# kalypso-usb-v1.net
KiCad netlist of a schematic drawn in EAGLE
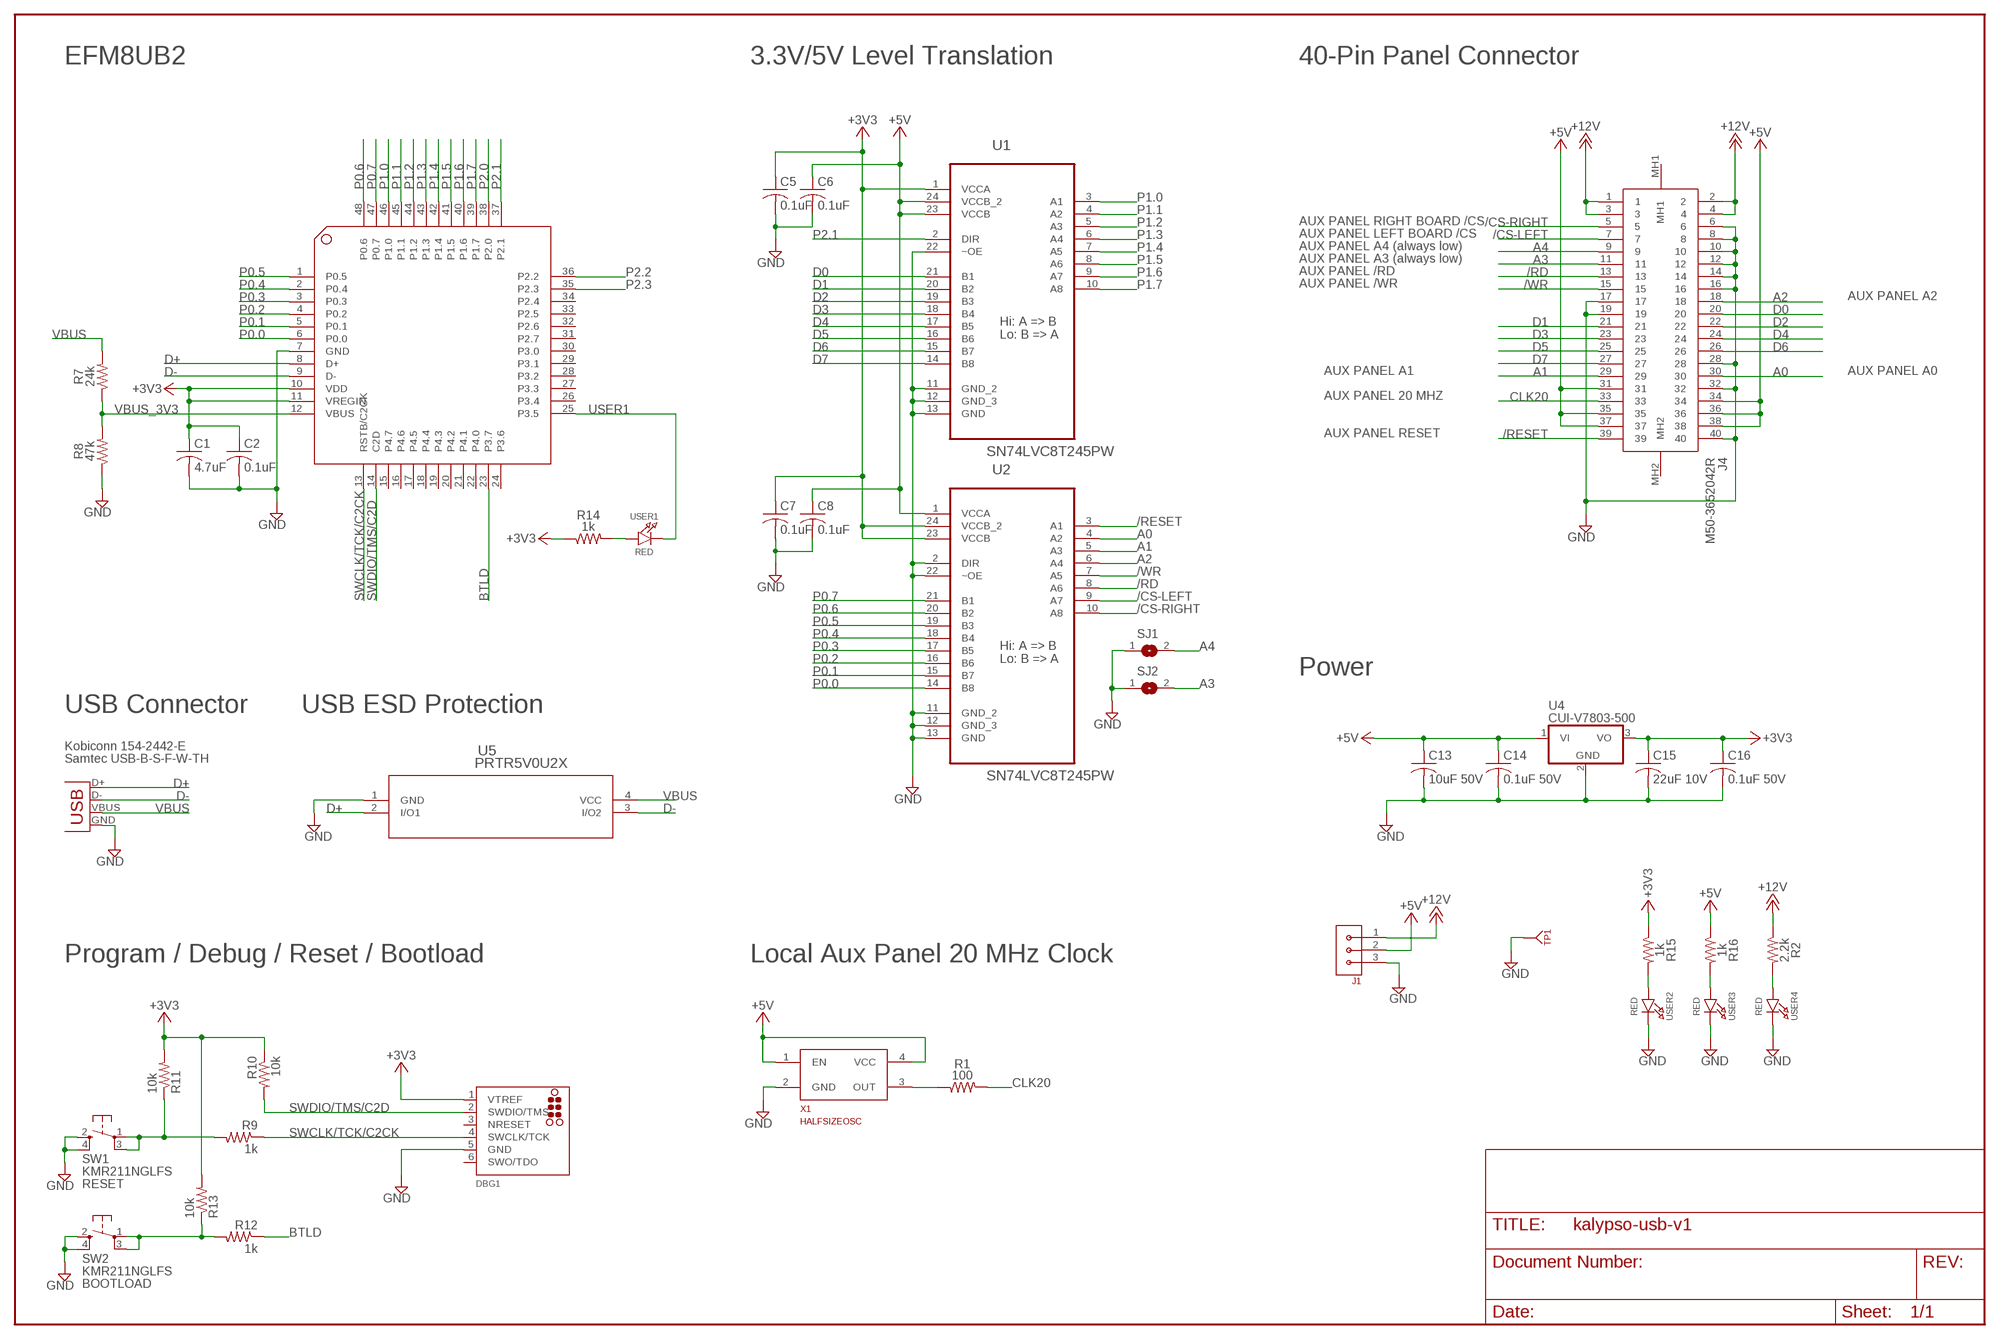
[diagram p0: schematic, sheet 1]

(export (version "E")
  (design (tool "Eeschema 10.0.6"))
  (components
    (comp (ref "C1")
      (value "4.7uF")
      (footprint "eagle-import:C0805K")
      (libsource (lib "eagle-import") (part "C-USC0805K"))
    )
    (comp (ref "C2")
      (value "0.1uF")
      (footprint "eagle-import:C0603K")
      (libsource (lib "eagle-import") (part "C-USC0603K"))
    )
    (comp (ref "C5")
      (value "0.1uF")
      (footprint "eagle-import:C0603K")
      (libsource (lib "eagle-import") (part "C-USC0603K"))
    )
    (comp (ref "C6")
      (value "0.1uF")
      (footprint "eagle-import:C0603K")
      (libsource (lib "eagle-import") (part "C-USC0603K"))
    )
    (comp (ref "C7")
      (value "0.1uF")
      (footprint "eagle-import:C0603K")
      (libsource (lib "eagle-import") (part "C-USC0603K"))
    )
    (comp (ref "C8")
      (value "0.1uF")
      (footprint "eagle-import:C0603K")
      (libsource (lib "eagle-import") (part "C-USC0603K"))
    )
    (comp (ref "C13")
      (value "10uF 50V")
      (footprint "eagle-import:C1210K")
      (fields (field (name "MFR") "KEMET") (field (name "MFR_PART_NO") "C1210C106K5RACTU"))
      (libsource (lib "eagle-import") (part "C-USC1210K"))
    )
    (comp (ref "C14")
      (value "0.1uF 50V")
      (footprint "eagle-import:C1206K")
      (fields (field (name "MFR") "KEMET") (field (name "MFR_PART_NO") "C1206S104M5RACTU"))
      (libsource (lib "eagle-import") (part "C-USC1206K"))
    )
    (comp (ref "C15")
      (value "22uF 10V")
      (footprint "eagle-import:C1206K")
      (fields (field (name "MFR") "KEMET") (field (name "MFR_PART_NO") "C1206C226K8RAC7800"))
      (libsource (lib "eagle-import") (part "C-USC1206K"))
    )
    (comp (ref "C16")
      (value "0.1uF 50V")
      (footprint "eagle-import:C1206K")
      (fields (field (name "MFR") "KEMET") (field (name "MFR_PART_NO") "C1206S104M5RACTU"))
      (libsource (lib "eagle-import") (part "C-USC1206K"))
    )
    (comp (ref "DBG1")
      (value "TC2030-CTX-SWD")
      (footprint "eagle-import:TC2030-MCP-NL")
      (libsource (lib "eagle-import") (part "TC2030-CTX-SWD"))
    )
    (comp (ref "J1")
      (value "CON-3.81MM-1X3-PHOENIX-RA")
      (footprint "eagle-import:CON-PHOENIX-3.81-1X3-RA")
      (libsource (lib "eagle-import") (part "CON-3.81MM-1X3-PHOENIX-RA"))
    )
    (comp (ref "J2")
      (value "USB-B")
      (footprint "eagle-import:USB-B-PTH")
      (fields (field (name "MFR") "KOBICONN") (field (name "MFR_PART_NO") "154-2442-E"))
      (libsource (lib "eagle-import") (part "USBPTH"))
    )
    (comp (ref "J4")
      (value "M50-3652042R")
      (footprint "eagle-import:M503652042R")
      (fields (field (name "MOUSER_PART_NUMBER") "855-M50-3652042R"))
      (libsource (lib "eagle-import") (part "M50-3652042R"))
    )
    (comp (ref "R1")
      (value "100")
      (footprint "eagle-import:R0603")
      (libsource (lib "eagle-import") (part "R-US_R0603"))
    )
    (comp (ref "R2")
      (value "2.2k")
      (footprint "eagle-import:R0603")
      (libsource (lib "eagle-import") (part "R-US_R0603"))
    )
    (comp (ref "R7")
      (value "24k")
      (footprint "eagle-import:R0603")
      (libsource (lib "eagle-import") (part "R-US_R0603"))
    )
    (comp (ref "R8")
      (value "47k")
      (footprint "eagle-import:R0603")
      (libsource (lib "eagle-import") (part "R-US_R0603"))
    )
    (comp (ref "R9")
      (value "1k")
      (footprint "eagle-import:R0603")
      (libsource (lib "eagle-import") (part "R-US_R0603"))
    )
    (comp (ref "R10")
      (value "10k")
      (footprint "eagle-import:R0603")
      (libsource (lib "eagle-import") (part "R-US_R0603"))
    )
    (comp (ref "R11")
      (value "10k")
      (footprint "eagle-import:R0603")
      (libsource (lib "eagle-import") (part "R-US_R0603"))
    )
    (comp (ref "R12")
      (value "1k")
      (footprint "eagle-import:R0603")
      (libsource (lib "eagle-import") (part "R-US_R0603"))
    )
    (comp (ref "R13")
      (value "10k")
      (footprint "eagle-import:R0603")
      (libsource (lib "eagle-import") (part "R-US_R0603"))
    )
    (comp (ref "R14")
      (value "1k")
      (footprint "eagle-import:R0603")
      (libsource (lib "eagle-import") (part "R-US_R0603"))
    )
    (comp (ref "R15")
      (value "1k")
      (footprint "eagle-import:R0603")
      (libsource (lib "eagle-import") (part "R-US_R0603"))
    )
    (comp (ref "R16")
      (value "1k")
      (footprint "eagle-import:R0603")
      (libsource (lib "eagle-import") (part "R-US_R0603"))
    )
    (comp (ref "SJ1") (value "SJ") (footprint "eagle-import:SJ") (libsource (lib "eagle-import") (part "SJ")))
    (comp (ref "SJ2") (value "SJ") (footprint "eagle-import:SJ") (libsource (lib "eagle-import") (part "SJ")))
    (comp (ref "SW1")
      (value "KMR211NGLFS")
      (footprint "eagle-import:KMR2")
      (libsource (lib "eagle-import") (part "SPST_TACT-KMR2"))
    )
    (comp (ref "SW2")
      (value "KMR211NGLFS")
      (footprint "eagle-import:KMR2")
      (libsource (lib "eagle-import") (part "SPST_TACT-KMR2"))
    )
    (comp (ref "TP1")
      (value "KEYSTONE_500X")
      (footprint "eagle-import:KEYSTONE_TP500X")
      (libsource (lib "eagle-import") (part "KEYSTONE_500X"))
    )
    (comp (ref "U1")
      (value "SN74LVC8T245PW")
      (footprint "eagle-import:SOP65P640X120-24N")
      (fields (field (name "MPN") "SN74AVC8T245PW"))
      (libsource (lib "eagle-import") (part "SN74AVC8T245PW"))
    )
    (comp (ref "U2")
      (value "SN74LVC8T245PW")
      (footprint "eagle-import:SOP65P640X120-24N")
      (fields (field (name "MPN") "SN74AVC8T245PW"))
      (libsource (lib "eagle-import") (part "SN74AVC8T245PW"))
    )
    (comp (ref "U4")
      (value "CUI-V7803-500")
      (footprint "eagle-import:CUI-78XX-500")
      (libsource (lib "eagle-import") (part "CUI-V7803-500"))
    )
    (comp (ref "U5")
      (value "PRTR5V0U2X")
      (footprint "eagle-import:SOT143B")
      (libsource (lib "eagle-import") (part "PRTR5V0U2X"))
    )
    (comp (ref "U6")
      (value "EFM8UB20F64G-B-QFP48")
      (footprint "eagle-import:EFM8UB2-QFP48")
      (libsource (lib "eagle-import") (part "EFM8UB20F64G-B-QFP48"))
    )
    (comp (ref "USER1")
      (value "RED")
      (footprint "eagle-import:CHIPLED_0805_NOOUTLINE")
      (libsource (lib "eagle-import") (part "LED0805_NOOUTLINE"))
    )
    (comp (ref "USER2")
      (value "RED")
      (footprint "eagle-import:CHIPLED_0805_NOOUTLINE")
      (libsource (lib "eagle-import") (part "LED0805_NOOUTLINE"))
    )
    (comp (ref "USER3")
      (value "RED")
      (footprint "eagle-import:CHIPLED_0805_NOOUTLINE")
      (libsource (lib "eagle-import") (part "LED0805_NOOUTLINE"))
    )
    (comp (ref "USER4")
      (value "RED")
      (footprint "eagle-import:CHIPLED_0805_NOOUTLINE")
      (libsource (lib "eagle-import") (part "LED0805_NOOUTLINE"))
    )
    (comp (ref "X1")
      (value "HALFSIZEOSC")
      (footprint "eagle-import:HALFSIZEOSC")
      (libsource (lib "eagle-import") (part "HALFSIZEOSC"))
    )
  )
  (nets
    (net (code "1") (name "+3V3") (class "Default")
      (node (ref "C1") (pin "1") (pinfunction "1_1") (pintype "passive"))
      (node (ref "C15") (pin "1") (pinfunction "1_1") (pintype "passive"))
      (node (ref "C16") (pin "1") (pinfunction "1_1") (pintype "passive"))
      (node (ref "C2") (pin "1") (pinfunction "1_1") (pintype "passive"))
      (node (ref "C5") (pin "1") (pinfunction "1_1") (pintype "passive"))
      (node (ref "C7") (pin "1") (pinfunction "1_1") (pintype "passive"))
      (node (ref "DBG1") (pin "1") (pinfunction "VTREF_1") (pintype "passive"))
      (node (ref "R10") (pin "1") (pinfunction "1_1") (pintype "passive"))
      (node (ref "R11") (pin "2") (pinfunction "2_2") (pintype "passive"))
      (node (ref "R13") (pin "2") (pinfunction "2_2") (pintype "passive"))
      (node (ref "R14") (pin "1") (pinfunction "1_1") (pintype "passive"))
      (node (ref "R15") (pin "1") (pinfunction "1_1") (pintype "passive"))
      (node (ref "U1") (pin "1") (pinfunction "VCCA_1") (pintype "power_in"))
      (node (ref "U2") (pin "23") (pinfunction "VCCB_23") (pintype "power_in"))
      (node (ref "U2") (pin "24") (pinfunction "VCCB_2_24") (pintype "power_in"))
      (node (ref "U4") (pin "3") (pinfunction "VO_3") (pintype "passive"))
      (node (ref "U6") (pin "10") (pinfunction "VDD_10") (pintype "bidirectional"))
      (node (ref "U6") (pin "11") (pinfunction "VREGIN_11") (pintype "bidirectional"))
    )
    (net (code "2") (name "+5V") (class "Default")
      (node (ref "C13") (pin "1") (pinfunction "1_1") (pintype "passive"))
      (node (ref "C14") (pin "1") (pinfunction "1_1") (pintype "passive"))
      (node (ref "C6") (pin "1") (pinfunction "1_1") (pintype "passive"))
      (node (ref "C8") (pin "1") (pinfunction "1_1") (pintype "passive"))
      (node (ref "J1") (pin "2") (pinfunction "2_2") (pintype "bidirectional"))
      (node (ref "J4") (pin "31") (pinfunction "31_31") (pintype "bidirectional"))
      (node (ref "J4") (pin "34") (pinfunction "34_34") (pintype "bidirectional"))
      (node (ref "J4") (pin "35") (pinfunction "35_35") (pintype "bidirectional"))
      (node (ref "J4") (pin "36") (pinfunction "36_36") (pintype "bidirectional"))
      (node (ref "J4") (pin "37") (pinfunction "37_37") (pintype "bidirectional"))
      (node (ref "J4") (pin "38") (pinfunction "38_38") (pintype "bidirectional"))
      (node (ref "R16") (pin "1") (pinfunction "1_1") (pintype "passive"))
      (node (ref "U1") (pin "23") (pinfunction "VCCB_23") (pintype "power_in"))
      (node (ref "U1") (pin "24") (pinfunction "VCCB_2_24") (pintype "power_in"))
      (node (ref "U2") (pin "1") (pinfunction "VCCA_1") (pintype "power_in"))
      (node (ref "U4") (pin "1") (pinfunction "VI_1") (pintype "input"))
      (node (ref "X1") (pin "1") (pinfunction "EN_1") (pintype "bidirectional"))
      (node (ref "X1") (pin "4") (pinfunction "VCC_4") (pintype "bidirectional"))
    )
    (net (code "3") (name "+12V") (class "Default")
      (node (ref "J1") (pin "1") (pinfunction "1_1") (pintype "bidirectional"))
      (node (ref "J4") (pin "1") (pinfunction "1_1") (pintype "bidirectional"))
      (node (ref "J4") (pin "2") (pinfunction "2_2") (pintype "bidirectional"))
      (node (ref "J4") (pin "3") (pinfunction "3_3") (pintype "bidirectional"))
      (node (ref "J4") (pin "4") (pinfunction "4_4") (pintype "bidirectional"))
      (node (ref "R2") (pin "1") (pinfunction "1_1") (pintype "passive"))
    )
    (net (code "4") (name "/A0") (class "Default")
      (node (ref "J4") (pin "30") (pinfunction "30_30") (pintype "bidirectional"))
      (node (ref "U2") (pin "4") (pinfunction "A2_4") (pintype "bidirectional"))
    )
    (net (code "5") (name "/A1") (class "Default")
      (node (ref "J4") (pin "29") (pinfunction "29_29") (pintype "bidirectional"))
      (node (ref "U2") (pin "5") (pinfunction "A3_5") (pintype "bidirectional"))
    )
    (net (code "6") (name "/A2") (class "Default")
      (node (ref "J4") (pin "18") (pinfunction "18_18") (pintype "bidirectional"))
      (node (ref "U2") (pin "6") (pinfunction "A4_6") (pintype "bidirectional"))
    )
    (net (code "7") (name "/A3") (class "Default")
      (node (ref "J4") (pin "11") (pinfunction "11_11") (pintype "bidirectional"))
      (node (ref "SJ2") (pin "2") (pinfunction "2_2") (pintype "passive"))
    )
    (net (code "8") (name "/A4") (class "Default")
      (node (ref "J4") (pin "9") (pinfunction "9_9") (pintype "bidirectional"))
      (node (ref "SJ1") (pin "2") (pinfunction "2_2") (pintype "passive"))
    )
    (net (code "9") (name "/BTLD") (class "Default")
      (node (ref "R12") (pin "1") (pinfunction "1_1") (pintype "passive"))
      (node (ref "U6") (pin "23") (pinfunction "P3.7_23") (pintype "bidirectional"))
    )
    (net (code "10") (name "/CLK20") (class "Default")
      (node (ref "J4") (pin "33") (pinfunction "33_33") (pintype "bidirectional"))
      (node (ref "R1") (pin "2") (pinfunction "2_2") (pintype "passive"))
    )
    (net (code "11") (name "/D+") (class "Default")
      (node (ref "J2") (pin "D+") (pinfunction "D+_D+") (pintype "bidirectional"))
      (node (ref "U5") (pin "2") (pinfunction "I/O1_2") (pintype "passive"))
      (node (ref "U6") (pin "8") (pinfunction "D+_8") (pintype "bidirectional"))
    )
    (net (code "12") (name "/D-") (class "Default")
      (node (ref "J2") (pin "D-") (pinfunction "D-_D-") (pintype "bidirectional"))
      (node (ref "U5") (pin "3") (pinfunction "I/O2_3") (pintype "passive"))
      (node (ref "U6") (pin "9") (pinfunction "D-_9") (pintype "bidirectional"))
    )
    (net (code "13") (name "/D0") (class "Default")
      (node (ref "J4") (pin "20") (pinfunction "20_20") (pintype "bidirectional"))
      (node (ref "U1") (pin "21") (pinfunction "B1_21") (pintype "bidirectional"))
    )
    (net (code "14") (name "/D1") (class "Default")
      (node (ref "J4") (pin "21") (pinfunction "21_21") (pintype "bidirectional"))
      (node (ref "U1") (pin "20") (pinfunction "B2_20") (pintype "bidirectional"))
    )
    (net (code "15") (name "/D2") (class "Default")
      (node (ref "J4") (pin "22") (pinfunction "22_22") (pintype "bidirectional"))
      (node (ref "U1") (pin "19") (pinfunction "B3_19") (pintype "bidirectional"))
    )
    (net (code "16") (name "/D3") (class "Default")
      (node (ref "J4") (pin "23") (pinfunction "23_23") (pintype "bidirectional"))
      (node (ref "U1") (pin "18") (pinfunction "B4_18") (pintype "bidirectional"))
    )
    (net (code "17") (name "/D4") (class "Default")
      (node (ref "J4") (pin "24") (pinfunction "24_24") (pintype "bidirectional"))
      (node (ref "U1") (pin "17") (pinfunction "B5_17") (pintype "bidirectional"))
    )
    (net (code "18") (name "/D5") (class "Default")
      (node (ref "J4") (pin "25") (pinfunction "25_25") (pintype "bidirectional"))
      (node (ref "U1") (pin "16") (pinfunction "B6_16") (pintype "bidirectional"))
    )
    (net (code "19") (name "/D6") (class "Default")
      (node (ref "J4") (pin "26") (pinfunction "26_26") (pintype "bidirectional"))
      (node (ref "U1") (pin "15") (pinfunction "B7_15") (pintype "bidirectional"))
    )
    (net (code "20") (name "/D7") (class "Default")
      (node (ref "J4") (pin "27") (pinfunction "27_27") (pintype "bidirectional"))
      (node (ref "U1") (pin "14") (pinfunction "B8_14") (pintype "bidirectional"))
    )
    (net (code "21") (name "/NRESET") (class "Default")
      (node (ref "DBG1") (pin "3") (pinfunction "NRESET_3") (pintype "power_in"))
    )
    (net (code "22") (name "/P0.0") (class "Default")
      (node (ref "U2") (pin "14") (pinfunction "B8_14") (pintype "bidirectional"))
      (node (ref "U6") (pin "6") (pinfunction "P0.0_6") (pintype "bidirectional"))
    )
    (net (code "23") (name "/P0.1") (class "Default")
      (node (ref "U2") (pin "15") (pinfunction "B7_15") (pintype "bidirectional"))
      (node (ref "U6") (pin "5") (pinfunction "P0.1_5") (pintype "bidirectional"))
    )
    (net (code "24") (name "/P0.2") (class "Default")
      (node (ref "U2") (pin "16") (pinfunction "B6_16") (pintype "bidirectional"))
      (node (ref "U6") (pin "4") (pinfunction "P0.2_4") (pintype "bidirectional"))
    )
    (net (code "25") (name "/P0.3") (class "Default")
      (node (ref "U2") (pin "17") (pinfunction "B5_17") (pintype "bidirectional"))
      (node (ref "U6") (pin "3") (pinfunction "P0.3_3") (pintype "bidirectional"))
    )
    (net (code "26") (name "/P0.4") (class "Default")
      (node (ref "U2") (pin "18") (pinfunction "B4_18") (pintype "bidirectional"))
      (node (ref "U6") (pin "2") (pinfunction "P0.4_2") (pintype "bidirectional"))
    )
    (net (code "27") (name "/P0.5") (class "Default")
      (node (ref "U2") (pin "19") (pinfunction "B3_19") (pintype "bidirectional"))
      (node (ref "U6") (pin "1") (pinfunction "P0.5_1") (pintype "bidirectional"))
    )
    (net (code "28") (name "/P0.6") (class "Default")
      (node (ref "U2") (pin "20") (pinfunction "B2_20") (pintype "bidirectional"))
      (node (ref "U6") (pin "48") (pinfunction "P0.6_48") (pintype "bidirectional"))
    )
    (net (code "29") (name "/P0.7") (class "Default")
      (node (ref "U2") (pin "21") (pinfunction "B1_21") (pintype "bidirectional"))
      (node (ref "U6") (pin "47") (pinfunction "P0.7_47") (pintype "bidirectional"))
    )
    (net (code "30") (name "/P1.0") (class "Default")
      (node (ref "U1") (pin "3") (pinfunction "A1_3") (pintype "bidirectional"))
      (node (ref "U6") (pin "46") (pinfunction "P1.0_46") (pintype "bidirectional"))
    )
    (net (code "31") (name "/P1.1") (class "Default")
      (node (ref "U1") (pin "4") (pinfunction "A2_4") (pintype "bidirectional"))
      (node (ref "U6") (pin "45") (pinfunction "P1.1_45") (pintype "bidirectional"))
    )
    (net (code "32") (name "/P1.2") (class "Default")
      (node (ref "U1") (pin "5") (pinfunction "A3_5") (pintype "bidirectional"))
      (node (ref "U6") (pin "44") (pinfunction "P1.2_44") (pintype "bidirectional"))
    )
    (net (code "33") (name "/P1.3") (class "Default")
      (node (ref "U1") (pin "6") (pinfunction "A4_6") (pintype "bidirectional"))
      (node (ref "U6") (pin "43") (pinfunction "P1.3_43") (pintype "bidirectional"))
    )
    (net (code "34") (name "/P1.4") (class "Default")
      (node (ref "U1") (pin "7") (pinfunction "A5_7") (pintype "bidirectional"))
      (node (ref "U6") (pin "42") (pinfunction "P1.4_42") (pintype "bidirectional"))
    )
    (net (code "35") (name "/P1.5") (class "Default")
      (node (ref "U1") (pin "8") (pinfunction "A6_8") (pintype "bidirectional"))
      (node (ref "U6") (pin "41") (pinfunction "P1.5_41") (pintype "bidirectional"))
    )
    (net (code "36") (name "/P1.6") (class "Default")
      (node (ref "U1") (pin "9") (pinfunction "A7_9") (pintype "bidirectional"))
      (node (ref "U6") (pin "40") (pinfunction "P1.6_40") (pintype "bidirectional"))
    )
    (net (code "37") (name "/P1.7") (class "Default")
      (node (ref "U1") (pin "10") (pinfunction "A8_10") (pintype "bidirectional"))
      (node (ref "U6") (pin "39") (pinfunction "P1.7_39") (pintype "bidirectional"))
    )
    (net (code "38") (name "/P2.0") (class "Default")
      (node (ref "U6") (pin "38") (pinfunction "P2.0_38") (pintype "bidirectional"))
    )
    (net (code "39") (name "/P2.1") (class "Default")
      (node (ref "U1") (pin "2") (pinfunction "DIR_2") (pintype "input"))
      (node (ref "U6") (pin "37") (pinfunction "P2.1_37") (pintype "bidirectional"))
    )
    (net (code "40") (name "/P2.2") (class "Default")
      (node (ref "U6") (pin "36") (pinfunction "P2.2_36") (pintype "bidirectional"))
    )
    (net (code "41") (name "/P2.3") (class "Default")
      (node (ref "U6") (pin "35") (pinfunction "P2.3_35") (pintype "bidirectional"))
    )
    (net (code "42") (name "/SWCLK{slash}TCK{slash}C2CK") (class "Default")
      (node (ref "DBG1") (pin "4") (pinfunction "SWCLK/TCK_4") (pintype "bidirectional"))
      (node (ref "R9") (pin "1") (pinfunction "1_1") (pintype "passive"))
      (node (ref "U6") (pin "13") (pinfunction "RSTB/C2CK_13") (pintype "bidirectional"))
    )
    (net (code "43") (name "/SWDIO{slash}TMS{slash}C2D") (class "Default")
      (node (ref "DBG1") (pin "2") (pinfunction "SWDIO/TMS_2") (pintype "power_in"))
      (node (ref "R10") (pin "2") (pinfunction "2_2") (pintype "passive"))
      (node (ref "U6") (pin "14") (pinfunction "C2D_14") (pintype "bidirectional"))
    )
    (net (code "44") (name "/USER1") (class "Default")
      (node (ref "U6") (pin "25") (pinfunction "P3.5_25") (pintype "bidirectional"))
      (node (ref "USER1") (pin "C") (pinfunction "C_C") (pintype "passive"))
    )
    (net (code "45") (name "/VBUS") (class "Default")
      (node (ref "J2") (pin "VBUS") (pinfunction "VBUS_VBUS") (pintype "bidirectional"))
      (node (ref "R7") (pin "2") (pinfunction "2_2") (pintype "passive"))
      (node (ref "U5") (pin "4") (pinfunction "VCC_4") (pintype "passive"))
    )
    (net (code "46") (name "/VBUS_3V3") (class "Default")
      (node (ref "R7") (pin "1") (pinfunction "1_1") (pintype "passive"))
      (node (ref "R8") (pin "2") (pinfunction "2_2") (pintype "passive"))
      (node (ref "U6") (pin "12") (pinfunction "VBUS_12") (pintype "bidirectional"))
    )
    (net (code "47") (name "/{slash}CS-LEFT") (class "Default")
      (node (ref "J4") (pin "7") (pinfunction "7_7") (pintype "bidirectional"))
      (node (ref "U2") (pin "9") (pinfunction "A7_9") (pintype "bidirectional"))
    )
    (net (code "48") (name "/{slash}CS-RIGHT") (class "Default")
      (node (ref "J4") (pin "5") (pinfunction "5_5") (pintype "bidirectional"))
      (node (ref "U2") (pin "10") (pinfunction "A8_10") (pintype "bidirectional"))
    )
    (net (code "49") (name "/{slash}RD") (class "Default")
      (node (ref "J4") (pin "13") (pinfunction "13_13") (pintype "bidirectional"))
      (node (ref "U2") (pin "8") (pinfunction "A6_8") (pintype "bidirectional"))
    )
    (net (code "50") (name "/{slash}RESET") (class "Default")
      (node (ref "J4") (pin "39") (pinfunction "39_39") (pintype "bidirectional"))
      (node (ref "U2") (pin "3") (pinfunction "A1_3") (pintype "bidirectional"))
    )
    (net (code "51") (name "/{slash}WR") (class "Default")
      (node (ref "J4") (pin "15") (pinfunction "15_15") (pintype "bidirectional"))
      (node (ref "U2") (pin "7") (pinfunction "A5_7") (pintype "bidirectional"))
    )
    (net (code "52") (name "GND") (class "Default")
      (node (ref "C1") (pin "2") (pinfunction "2_2") (pintype "passive"))
      (node (ref "C13") (pin "2") (pinfunction "2_2") (pintype "passive"))
      (node (ref "C14") (pin "2") (pinfunction "2_2") (pintype "passive"))
      (node (ref "C15") (pin "2") (pinfunction "2_2") (pintype "passive"))
      (node (ref "C16") (pin "2") (pinfunction "2_2") (pintype "passive"))
      (node (ref "C2") (pin "2") (pinfunction "2_2") (pintype "passive"))
      (node (ref "C5") (pin "2") (pinfunction "2_2") (pintype "passive"))
      (node (ref "C6") (pin "2") (pinfunction "2_2") (pintype "passive"))
      (node (ref "C7") (pin "2") (pinfunction "2_2") (pintype "passive"))
      (node (ref "C8") (pin "2") (pinfunction "2_2") (pintype "passive"))
      (node (ref "DBG1") (pin "5") (pinfunction "GND_5") (pintype "output"))
      (node (ref "J1") (pin "3") (pinfunction "3_3") (pintype "bidirectional"))
      (node (ref "J2") (pin "GND") (pinfunction "GND_GND") (pintype "bidirectional"))
      (node (ref "J4") (pin "10") (pinfunction "10_10") (pintype "bidirectional"))
      (node (ref "J4") (pin "12") (pinfunction "12_12") (pintype "bidirectional"))
      (node (ref "J4") (pin "14") (pinfunction "14_14") (pintype "bidirectional"))
      (node (ref "J4") (pin "16") (pinfunction "16_16") (pintype "bidirectional"))
      (node (ref "J4") (pin "17") (pinfunction "17_17") (pintype "bidirectional"))
      (node (ref "J4") (pin "19") (pinfunction "19_19") (pintype "bidirectional"))
      (node (ref "J4") (pin "28") (pinfunction "28_28") (pintype "bidirectional"))
      (node (ref "J4") (pin "32") (pinfunction "32_32") (pintype "bidirectional"))
      (node (ref "J4") (pin "40") (pinfunction "40_40") (pintype "bidirectional"))
      (node (ref "J4") (pin "6") (pinfunction "6_6") (pintype "bidirectional"))
      (node (ref "J4") (pin "8") (pinfunction "8_8") (pintype "bidirectional"))
      (node (ref "R8") (pin "1") (pinfunction "1_1") (pintype "passive"))
      (node (ref "SJ1") (pin "1") (pinfunction "1_1") (pintype "passive"))
      (node (ref "SJ2") (pin "1") (pinfunction "1_1") (pintype "passive"))
      (node (ref "SW1") (pin "2") (pinfunction "S_2") (pintype "passive"))
      (node (ref "SW1") (pin "4") (pinfunction "S1_4") (pintype "passive"))
      (node (ref "SW2") (pin "2") (pinfunction "S_2") (pintype "passive"))
      (node (ref "SW2") (pin "4") (pinfunction "S1_4") (pintype "passive"))
      (node (ref "TP1") (pin "1") (pinfunction "P$1_1") (pintype "bidirectional"))
      (node (ref "U1") (pin "11") (pinfunction "GND_2_11") (pintype "passive"))
      (node (ref "U1") (pin "12") (pinfunction "GND_3_12") (pintype "passive"))
      (node (ref "U1") (pin "13") (pinfunction "GND_13") (pintype "passive"))
      (node (ref "U1") (pin "22") (pinfunction "~{OE}_22") (pintype "input"))
      (node (ref "U2") (pin "11") (pinfunction "GND_2_11") (pintype "passive"))
      (node (ref "U2") (pin "12") (pinfunction "GND_3_12") (pintype "passive"))
      (node (ref "U2") (pin "13") (pinfunction "GND_13") (pintype "passive"))
      (node (ref "U2") (pin "2") (pinfunction "DIR_2") (pintype "input"))
      (node (ref "U2") (pin "22") (pinfunction "~{OE}_22") (pintype "input"))
      (node (ref "U4") (pin "2") (pinfunction "GND_2") (pintype "passive"))
      (node (ref "U5") (pin "1") (pinfunction "GND_1") (pintype "passive"))
      (node (ref "U6") (pin "7") (pinfunction "GND_7") (pintype "bidirectional"))
      (node (ref "USER2") (pin "C") (pinfunction "C_C") (pintype "passive"))
      (node (ref "USER3") (pin "C") (pinfunction "C_C") (pintype "passive"))
      (node (ref "USER4") (pin "C") (pinfunction "C_C") (pintype "passive"))
      (node (ref "X1") (pin "2") (pinfunction "GND_2") (pintype "bidirectional"))
    )
    (net (code "53") (name "Net-(R2-Pad2)") (class "Default")
      (node (ref "R2") (pin "2") (pinfunction "2_2") (pintype "passive"))
      (node (ref "USER4") (pin "A") (pinfunction "A_A") (pintype "passive"))
    )
    (net (code "54") (name "Net-(R14-Pad2)") (class "Default")
      (node (ref "R14") (pin "2") (pinfunction "2_2") (pintype "passive"))
      (node (ref "USER1") (pin "A") (pinfunction "A_A") (pintype "passive"))
    )
    (net (code "55") (name "Net-(R15-Pad2)") (class "Default")
      (node (ref "R15") (pin "2") (pinfunction "2_2") (pintype "passive"))
      (node (ref "USER2") (pin "A") (pinfunction "A_A") (pintype "passive"))
    )
    (net (code "56") (name "Net-(R16-Pad2)") (class "Default")
      (node (ref "R16") (pin "2") (pinfunction "2_2") (pintype "passive"))
      (node (ref "USER3") (pin "A") (pinfunction "A_A") (pintype "passive"))
    )
    (net (code "57") (name "Net-(SW1-P)") (class "Default")
      (node (ref "R11") (pin "1") (pinfunction "1_1") (pintype "passive"))
      (node (ref "R9") (pin "2") (pinfunction "2_2") (pintype "passive"))
      (node (ref "SW1") (pin "1") (pinfunction "P_1") (pintype "passive"))
      (node (ref "SW1") (pin "3") (pinfunction "P1_3") (pintype "passive"))
    )
    (net (code "58") (name "Net-(SW2-P)") (class "Default")
      (node (ref "R12") (pin "2") (pinfunction "2_2") (pintype "passive"))
      (node (ref "R13") (pin "1") (pinfunction "1_1") (pintype "passive"))
      (node (ref "SW2") (pin "1") (pinfunction "P_1") (pintype "passive"))
      (node (ref "SW2") (pin "3") (pinfunction "P1_3") (pintype "passive"))
    )
    (net (code "59") (name "Net-(X1-OUT)") (class "Default")
      (node (ref "R1") (pin "1") (pinfunction "1_1") (pintype "passive"))
      (node (ref "X1") (pin "3") (pinfunction "OUT_3") (pintype "bidirectional"))
    )
    (net (code "60") (name "unconnected-(DBG1-SWO{slash}TDO-Pad6)") (class "Default")
      (node (ref "DBG1") (pin "6") (pinfunction "SWO/TDO_6") (pintype "bidirectional"))
    )
    (net (code "61") (name "unconnected-(J4-PadMH1)") (class "Default")
      (node (ref "J4") (pin "MH1") (pinfunction "MH1_MH1") (pintype "bidirectional"))
    )
    (net (code "62") (name "unconnected-(J4-PadMH2)") (class "Default")
      (node (ref "J4") (pin "MH2") (pinfunction "MH2_MH2") (pintype "bidirectional"))
    )
    (net (code "63") (name "unconnected-(U6-P2.4-Pad34)") (class "Default")
      (node (ref "U6") (pin "34") (pinfunction "P2.4_34") (pintype "bidirectional"))
    )
    (net (code "64") (name "unconnected-(U6-P2.5-Pad33)") (class "Default")
      (node (ref "U6") (pin "33") (pinfunction "P2.5_33") (pintype "bidirectional"))
    )
    (net (code "65") (name "unconnected-(U6-P2.6-Pad32)") (class "Default")
      (node (ref "U6") (pin "32") (pinfunction "P2.6_32") (pintype "bidirectional"))
    )
    (net (code "66") (name "unconnected-(U6-P2.7-Pad31)") (class "Default")
      (node (ref "U6") (pin "31") (pinfunction "P2.7_31") (pintype "bidirectional"))
    )
    (net (code "67") (name "unconnected-(U6-P3.0-Pad30)") (class "Default")
      (node (ref "U6") (pin "30") (pinfunction "P3.0_30") (pintype "bidirectional"))
    )
    (net (code "68") (name "unconnected-(U6-P3.1-Pad29)") (class "Default")
      (node (ref "U6") (pin "29") (pinfunction "P3.1_29") (pintype "bidirectional"))
    )
    (net (code "69") (name "unconnected-(U6-P3.2-Pad28)") (class "Default")
      (node (ref "U6") (pin "28") (pinfunction "P3.2_28") (pintype "bidirectional"))
    )
    (net (code "70") (name "unconnected-(U6-P3.3-Pad27)") (class "Default")
      (node (ref "U6") (pin "27") (pinfunction "P3.3_27") (pintype "bidirectional"))
    )
    (net (code "71") (name "unconnected-(U6-P3.4-Pad26)") (class "Default")
      (node (ref "U6") (pin "26") (pinfunction "P3.4_26") (pintype "bidirectional"))
    )
    (net (code "72") (name "unconnected-(U6-P3.6-Pad24)") (class "Default")
      (node (ref "U6") (pin "24") (pinfunction "P3.6_24") (pintype "bidirectional"))
    )
    (net (code "73") (name "unconnected-(U6-P4.0-Pad22)") (class "Default")
      (node (ref "U6") (pin "22") (pinfunction "P4.0_22") (pintype "bidirectional"))
    )
    (net (code "74") (name "unconnected-(U6-P4.1-Pad21)") (class "Default")
      (node (ref "U6") (pin "21") (pinfunction "P4.1_21") (pintype "bidirectional"))
    )
    (net (code "75") (name "unconnected-(U6-P4.2-Pad20)") (class "Default")
      (node (ref "U6") (pin "20") (pinfunction "P4.2_20") (pintype "bidirectional"))
    )
    (net (code "76") (name "unconnected-(U6-P4.3-Pad19)") (class "Default")
      (node (ref "U6") (pin "19") (pinfunction "P4.3_19") (pintype "bidirectional"))
    )
    (net (code "77") (name "unconnected-(U6-P4.4-Pad18)") (class "Default")
      (node (ref "U6") (pin "18") (pinfunction "P4.4_18") (pintype "bidirectional"))
    )
    (net (code "78") (name "unconnected-(U6-P4.5-Pad17)") (class "Default")
      (node (ref "U6") (pin "17") (pinfunction "P4.5_17") (pintype "bidirectional"))
    )
    (net (code "79") (name "unconnected-(U6-P4.6-Pad16)") (class "Default")
      (node (ref "U6") (pin "16") (pinfunction "P4.6_16") (pintype "bidirectional"))
    )
    (net (code "80") (name "unconnected-(U6-P4.7-Pad15)") (class "Default")
      (node (ref "U6") (pin "15") (pinfunction "P4.7_15") (pintype "bidirectional"))
    )
  )
)
